# onThyristor.net
KiCad netlist of a schematic drawn in Altium Designer
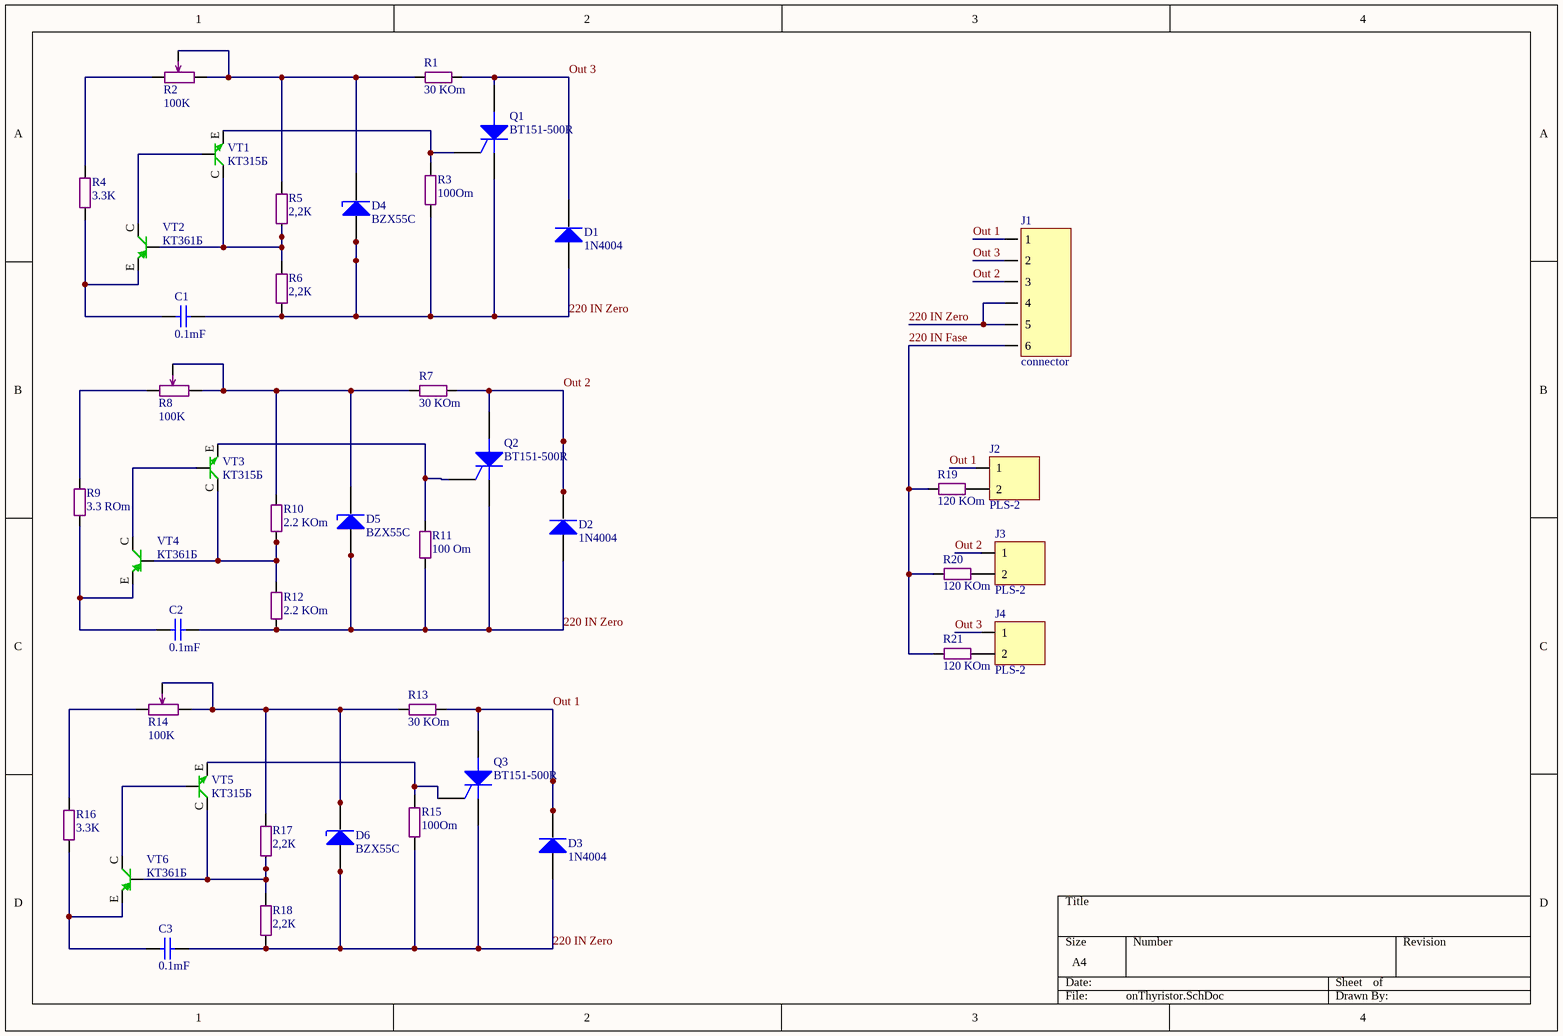
[diagram p0: onThyristor.SchDoc]

(export (version "E")
  (design (tool "Eeschema 10.0.6"))
  (components
    (comp (ref "C1")
      (value "0.1mF")
      (footprint "Capacitor:Cap P5.08MM (3p) disk2")
      (description "Capacitor")
      (libsource (lib "Capacitor") (part "Cap Ceramic"))
    )
    (comp (ref "C2")
      (value "0.1mF")
      (footprint "Capacitor:Cap P5.08MM (3p) disk2")
      (description "Capacitor")
      (libsource (lib "Capacitor") (part "Cap Ceramic"))
    )
    (comp (ref "C3")
      (value "0.1mF")
      (footprint "Capacitor:Cap P5.08MM (3p) disk2")
      (description "Capacitor")
      (libsource (lib "Capacitor") (part "Cap Ceramic"))
    )
    (comp (ref "D1")
      (value "1N4004")
      (footprint "Diodes:Diode DO-35")
      (description "1 Amp General Purpose Rectifier")
      (libsource (lib "Diodes") (part "Diode 1N4004"))
    )
    (comp (ref "D2")
      (value "1N4004")
      (footprint "Diodes:Diode DO-35")
      (description "1 Amp General Purpose Rectifier")
      (libsource (lib "Diodes") (part "Diode 1N4004"))
    )
    (comp (ref "D3")
      (value "1N4004")
      (footprint "Diodes:Diode DO-35")
      (description "1 Amp General Purpose Rectifier")
      (libsource (lib "Diodes") (part "Diode 1N4004"))
    )
    (comp (ref "D4")
      (value "BZX55C")
      (footprint "Diodes:Diode DO-35")
      (description "1 Amp General Purpose Rectifier")
      (libsource (lib "Diodes") (part "Stabistor BZX55C"))
    )
    (comp (ref "D5")
      (value "BZX55C")
      (footprint "Diodes:Diode DO-35")
      (description "1 Amp General Purpose Rectifier")
      (libsource (lib "Diodes") (part "Stabistor BZX55C"))
    )
    (comp (ref "D6")
      (value "BZX55C")
      (footprint "Diodes:Diode DO-35")
      (description "1 Amp General Purpose Rectifier")
      (libsource (lib "Diodes") (part "Stabistor BZX55C"))
    )
    (comp (ref "J1")
      (value "connector")
      (footprint "Connector:Molex Mini-Fit Jr - 6Pin R")
      (description "Right, Dbl line, Female")
      (libsource (lib "Connector") (part "Molex Mini-Fit Jr - 6 pin - R"))
    )
    (comp (ref "J2")
      (value "PLS-2")
      (footprint "Connector:Line 2.54 x 2")
      (description "Vert, Sgl line, Male")
      (libsource (lib "Connector") (part "PLS-2"))
    )
    (comp (ref "J3")
      (value "PLS-2")
      (footprint "Connector:Line 2.54 x 2")
      (description "Vert, Sgl line, Male")
      (libsource (lib "Connector") (part "PLS-2"))
    )
    (comp (ref "J4")
      (value "PLS-2")
      (footprint "Connector:Line 2.54 x 2")
      (description "Vert, Sgl line, Male")
      (libsource (lib "Connector") (part "PLS-2"))
    )
    (comp (ref "Q1")
      (value "BT151-500R")
      (footprint "GeneralCases:TO220-2")
      (description "Thyristor")
      (libsource (lib "Diodes") (part "Th BT151-500R"))
    )
    (comp (ref "Q2")
      (value "BT151-500R")
      (footprint "GeneralCases:TO220-2")
      (description "Thyristor")
      (libsource (lib "Diodes") (part "Th BT151-500R"))
    )
    (comp (ref "Q3")
      (value "BT151-500R")
      (footprint "GeneralCases:TO220-2")
      (description "Thyristor")
      (libsource (lib "Diodes") (part "Th BT151-500R"))
    )
    (comp (ref "R1")
      (value "30 KOm")
      (footprint "PassiveComponents:Res 5W L22mm, p30mm")
      (description "5W Cement")
      (libsource (lib "PassiveComponents") (part "Res 5W"))
    )
    (comp (ref "R2")
      (value "100K")
      (footprint "bj Lib:PinLine 3x")
      (libsource (lib "bj Lib") (part "Resistor Adj"))
    )
    (comp (ref "R3")
      (value "100Om")
      (footprint "PassiveComponents:Res p7.62 (4p) 0.25w")
      (libsource (lib "bj Lib") (part "Resistor"))
    )
    (comp (ref "R4")
      (value "3.3K")
      (footprint "PassiveComponents:Res p7.62 (4p) 0.25w")
      (libsource (lib "bj Lib") (part "Resistor"))
    )
    (comp (ref "R5")
      (value "2,2К")
      (footprint "PassiveComponents:Res p7.62 (4p) 0.25w")
      (libsource (lib "bj Lib") (part "Resistor"))
    )
    (comp (ref "R6")
      (value "2,2К")
      (footprint "PassiveComponents:Res p7.62 (4p) 0.25w")
      (libsource (lib "bj Lib") (part "Resistor"))
    )
    (comp (ref "R7")
      (value "30 KOm")
      (footprint "PassiveComponents:Res 5W L22mm, p30mm")
      (description "5W Cement")
      (libsource (lib "PassiveComponents") (part "Res 5W"))
    )
    (comp (ref "R8")
      (value "100K")
      (footprint "bj Lib:PinLine 3x")
      (libsource (lib "bj Lib") (part "Resistor Adj"))
    )
    (comp (ref "R9")
      (value "3.3 ROm")
      (footprint "PassiveComponents:Res p7.62 (4p) 0.25w")
      (libsource (lib "PassiveComponents") (part "Res SMD 0603"))
    )
    (comp (ref "R10")
      (value "2.2 KOm")
      (footprint "PassiveComponents:Res p7.62 (4p) 0.25w")
      (libsource (lib "PassiveComponents") (part "Res SMD 0603"))
    )
    (comp (ref "R11")
      (value "100 Om")
      (footprint "PassiveComponents:Res p7.62 (4p) 0.25w")
      (libsource (lib "PassiveComponents") (part "Res SMD 0603"))
    )
    (comp (ref "R12")
      (value "2.2 KOm")
      (footprint "PassiveComponents:Res p7.62 (4p) 0.25w")
      (libsource (lib "PassiveComponents") (part "Res SMD 0603"))
    )
    (comp (ref "R13")
      (value "30 KOm")
      (footprint "PassiveComponents:Res 5W L22mm, p30mm")
      (description "5W Cement")
      (libsource (lib "PassiveComponents") (part "Res 5W"))
    )
    (comp (ref "R14")
      (value "100K")
      (footprint "bj Lib:PinLine 3x")
      (libsource (lib "bj Lib") (part "Resistor Adj"))
    )
    (comp (ref "R15")
      (value "100Om")
      (footprint "PassiveComponents:SMD 0805 (2012)")
      (libsource (lib "bj Lib") (part "Resistor"))
    )
    (comp (ref "R16")
      (value "3.3K")
      (footprint "PassiveComponents:Res p7.62 (4p) 0.25w")
      (libsource (lib "bj Lib") (part "Resistor"))
    )
    (comp (ref "R17")
      (value "2,2К")
      (footprint "PassiveComponents:Res p7.62 (4p) 0.25w")
      (libsource (lib "bj Lib") (part "Resistor"))
    )
    (comp (ref "R18")
      (value "2,2К")
      (footprint "bj Lib:Res p7.62 (4p)")
      (libsource (lib "bj Lib") (part "Resistor"))
    )
    (comp (ref "R19")
      (value "120 KOm")
      (footprint "PassiveComponents:SMD 1206 (3216)")
      (libsource (lib "PassiveComponents") (part "Res Carbon"))
    )
    (comp (ref "R20")
      (value "120 KOm")
      (footprint "PassiveComponents:SMD 1206 (3216)")
      (libsource (lib "PassiveComponents") (part "Res Carbon"))
    )
    (comp (ref "R21")
      (value "120 KOm")
      (footprint "PassiveComponents:SMD 1206 (3216)")
      (libsource (lib "PassiveComponents") (part "Res Carbon"))
    )
    (comp (ref "VT1") (value "КТ315Б") (footprint "Trnstr (3p) ECB") (libsource (lib "bj Lib") (part "NPN")))
    (comp (ref "VT2")
      (value "КТ361Б")
      (footprint "bj Lib:Trnstr (3p) ECB")
      (libsource (lib "bj Lib") (part "PNP"))
    )
    (comp (ref "VT3") (value "КТ315Б") (footprint "Trnstr (3p) ECB") (libsource (lib "bj Lib") (part "NPN")))
    (comp (ref "VT4")
      (value "КТ361Б")
      (footprint "bj Lib:Trnstr (3p) ECB")
      (libsource (lib "bj Lib") (part "PNP"))
    )
    (comp (ref "VT5") (value "КТ315Б") (footprint "Trnstr (3p) ECB") (libsource (lib "bj Lib") (part "NPN")))
    (comp (ref "VT6")
      (value "КТ361Б")
      (footprint "bj Lib:Trnstr (3p) ECB")
      (libsource (lib "bj Lib") (part "PNP"))
    )
  )
  (nets
    (net (code "1") (name "/220 IN Fase") (class "Default")
      (node (ref "J1") (pin "6") (pinfunction "6_6") (pintype "passive"))
      (node (ref "R19") (pin "1") (pinfunction "1_1") (pintype "passive"))
      (node (ref "R20") (pin "1") (pinfunction "1_1") (pintype "passive"))
      (node (ref "R21") (pin "1") (pinfunction "1_1") (pintype "passive"))
    )
    (net (code "2") (name "/220 IN Zero") (class "Default")
      (node (ref "C1") (pin "2") (pinfunction "2_2") (pintype "passive"))
      (node (ref "C2") (pin "2") (pinfunction "2_2") (pintype "passive"))
      (node (ref "C3") (pin "2") (pinfunction "2_2") (pintype "passive"))
      (node (ref "D1") (pin "A") (pinfunction "A_A") (pintype "passive"))
      (node (ref "D2") (pin "A") (pinfunction "A_A") (pintype "passive"))
      (node (ref "D3") (pin "A") (pinfunction "A_A") (pintype "passive"))
      (node (ref "D4") (pin "A") (pinfunction "A_A") (pintype "passive"))
      (node (ref "D5") (pin "A") (pinfunction "A_A") (pintype "passive"))
      (node (ref "D6") (pin "A") (pinfunction "A_A") (pintype "passive"))
      (node (ref "J1") (pin "4") (pinfunction "4_4") (pintype "passive"))
      (node (ref "J1") (pin "5") (pinfunction "5_5") (pintype "passive"))
      (node (ref "Q1") (pin "1") (pinfunction "K_1") (pintype "passive"))
      (node (ref "Q2") (pin "1") (pinfunction "K_1") (pintype "passive"))
      (node (ref "Q3") (pin "1") (pinfunction "K_1") (pintype "passive"))
      (node (ref "R11") (pin "1") (pinfunction "1_1") (pintype "passive"))
      (node (ref "R12") (pin "1") (pinfunction "1_1") (pintype "passive"))
      (node (ref "R15") (pin "1") (pinfunction "1_1") (pintype "passive"))
      (node (ref "R18") (pin "1") (pinfunction "1_1") (pintype "passive"))
      (node (ref "R3") (pin "1") (pinfunction "1_1") (pintype "passive"))
      (node (ref "R6") (pin "1") (pinfunction "1_1") (pintype "passive"))
    )
    (net (code "3") (name "/Out 1") (class "Default")
      (node (ref "D3") (pin "K") (pinfunction "K_K") (pintype "passive"))
      (node (ref "J1") (pin "1") (pinfunction "1_1") (pintype "passive"))
      (node (ref "J2") (pin "1") (pinfunction "1_1") (pintype "passive"))
      (node (ref "Q3") (pin "2") (pinfunction "A_2") (pintype "passive"))
      (node (ref "R13") (pin "2") (pinfunction "2_2") (pintype "passive"))
    )
    (net (code "4") (name "/Out 2") (class "Default")
      (node (ref "D2") (pin "K") (pinfunction "K_K") (pintype "passive"))
      (node (ref "J1") (pin "3") (pinfunction "3_3") (pintype "passive"))
      (node (ref "J3") (pin "1") (pinfunction "1_1") (pintype "passive"))
      (node (ref "Q2") (pin "2") (pinfunction "A_2") (pintype "passive"))
      (node (ref "R7") (pin "2") (pinfunction "2_2") (pintype "passive"))
    )
    (net (code "5") (name "/Out 3") (class "Default")
      (node (ref "D1") (pin "K") (pinfunction "K_K") (pintype "passive"))
      (node (ref "J1") (pin "2") (pinfunction "2_2") (pintype "passive"))
      (node (ref "J4") (pin "1") (pinfunction "1_1") (pintype "passive"))
      (node (ref "Q1") (pin "2") (pinfunction "A_2") (pintype "passive"))
      (node (ref "R1") (pin "2") (pinfunction "2_2") (pintype "passive"))
    )
    (net (code "6") (name "Net-(C1-Pad1)") (class "Default")
      (node (ref "C1") (pin "1") (pinfunction "1_1") (pintype "passive"))
      (node (ref "R4") (pin "1") (pinfunction "1_1") (pintype "passive"))
      (node (ref "VT2") (pin "E") (pinfunction "E_E") (pintype "passive"))
    )
    (net (code "7") (name "Net-(C2-Pad1)") (class "Default")
      (node (ref "C2") (pin "1") (pinfunction "1_1") (pintype "passive"))
      (node (ref "R9") (pin "1") (pinfunction "1_1") (pintype "passive"))
      (node (ref "VT4") (pin "E") (pinfunction "E_E") (pintype "passive"))
    )
    (net (code "8") (name "Net-(C3-Pad1)") (class "Default")
      (node (ref "C3") (pin "1") (pinfunction "1_1") (pintype "passive"))
      (node (ref "R16") (pin "1") (pinfunction "1_1") (pintype "passive"))
      (node (ref "VT6") (pin "E") (pinfunction "E_E") (pintype "passive"))
    )
    (net (code "9") (name "Net-(D4-PadK)") (class "Default")
      (node (ref "D4") (pin "K") (pinfunction "K_K") (pintype "passive"))
      (node (ref "R1") (pin "1") (pinfunction "1_1") (pintype "passive"))
      (node (ref "R2") (pin "2") (pinfunction "2_2") (pintype "passive"))
      (node (ref "R2") (pin "3") (pinfunction "3_3") (pintype "passive"))
      (node (ref "R5") (pin "2") (pinfunction "2_2") (pintype "passive"))
    )
    (net (code "10") (name "Net-(D5-PadK)") (class "Default")
      (node (ref "D5") (pin "K") (pinfunction "K_K") (pintype "passive"))
      (node (ref "R10") (pin "2") (pinfunction "2_2") (pintype "passive"))
      (node (ref "R7") (pin "1") (pinfunction "1_1") (pintype "passive"))
      (node (ref "R8") (pin "2") (pinfunction "2_2") (pintype "passive"))
      (node (ref "R8") (pin "3") (pinfunction "3_3") (pintype "passive"))
    )
    (net (code "11") (name "Net-(D6-PadK)") (class "Default")
      (node (ref "D6") (pin "K") (pinfunction "K_K") (pintype "passive"))
      (node (ref "R13") (pin "1") (pinfunction "1_1") (pintype "passive"))
      (node (ref "R14") (pin "2") (pinfunction "2_2") (pintype "passive"))
      (node (ref "R14") (pin "3") (pinfunction "3_3") (pintype "passive"))
      (node (ref "R17") (pin "2") (pinfunction "2_2") (pintype "passive"))
    )
    (net (code "12") (name "Net-(J2-Pad2)") (class "Default")
      (node (ref "J2") (pin "2") (pinfunction "2_2") (pintype "passive"))
      (node (ref "R19") (pin "2") (pinfunction "2_2") (pintype "passive"))
    )
    (net (code "13") (name "Net-(J3-Pad2)") (class "Default")
      (node (ref "J3") (pin "2") (pinfunction "2_2") (pintype "passive"))
      (node (ref "R20") (pin "2") (pinfunction "2_2") (pintype "passive"))
    )
    (net (code "14") (name "Net-(J4-Pad2)") (class "Default")
      (node (ref "J4") (pin "2") (pinfunction "2_2") (pintype "passive"))
      (node (ref "R21") (pin "2") (pinfunction "2_2") (pintype "passive"))
    )
    (net (code "15") (name "Net-(Q1-G)") (class "Default")
      (node (ref "Q1") (pin "3") (pinfunction "G_3") (pintype "passive"))
      (node (ref "R3") (pin "2") (pinfunction "2_2") (pintype "passive"))
      (node (ref "VT1") (pin "E") (pinfunction "E_E") (pintype "passive"))
    )
    (net (code "16") (name "Net-(Q2-G)") (class "Default")
      (node (ref "Q2") (pin "3") (pinfunction "G_3") (pintype "passive"))
      (node (ref "R11") (pin "2") (pinfunction "2_2") (pintype "passive"))
      (node (ref "VT3") (pin "E") (pinfunction "E_E") (pintype "passive"))
    )
    (net (code "17") (name "Net-(Q3-G)") (class "Default")
      (node (ref "Q3") (pin "3") (pinfunction "G_3") (pintype "passive"))
      (node (ref "R15") (pin "2") (pinfunction "2_2") (pintype "passive"))
      (node (ref "VT5") (pin "E") (pinfunction "E_E") (pintype "passive"))
    )
    (net (code "18") (name "Net-(R2-Pad1)") (class "Default")
      (node (ref "R2") (pin "1") (pinfunction "1_1") (pintype "passive"))
      (node (ref "R4") (pin "2") (pinfunction "2_2") (pintype "passive"))
    )
    (net (code "19") (name "Net-(R5-Pad1)") (class "Default")
      (node (ref "R5") (pin "1") (pinfunction "1_1") (pintype "passive"))
      (node (ref "R6") (pin "2") (pinfunction "2_2") (pintype "passive"))
      (node (ref "VT1") (pin "C") (pinfunction "C_C") (pintype "passive"))
      (node (ref "VT2") (pin "B") (pinfunction "B_B") (pintype "passive"))
    )
    (net (code "20") (name "Net-(R8-Pad1)") (class "Default")
      (node (ref "R8") (pin "1") (pinfunction "1_1") (pintype "passive"))
      (node (ref "R9") (pin "2") (pinfunction "2_2") (pintype "passive"))
    )
    (net (code "21") (name "Net-(R10-Pad1)") (class "Default")
      (node (ref "R10") (pin "1") (pinfunction "1_1") (pintype "passive"))
      (node (ref "R12") (pin "2") (pinfunction "2_2") (pintype "passive"))
      (node (ref "VT3") (pin "C") (pinfunction "C_C") (pintype "passive"))
      (node (ref "VT4") (pin "B") (pinfunction "B_B") (pintype "passive"))
    )
    (net (code "22") (name "Net-(R14-Pad1)") (class "Default")
      (node (ref "R14") (pin "1") (pinfunction "1_1") (pintype "passive"))
      (node (ref "R16") (pin "2") (pinfunction "2_2") (pintype "passive"))
    )
    (net (code "23") (name "Net-(R17-Pad1)") (class "Default")
      (node (ref "R17") (pin "1") (pinfunction "1_1") (pintype "passive"))
      (node (ref "R18") (pin "2") (pinfunction "2_2") (pintype "passive"))
      (node (ref "VT5") (pin "C") (pinfunction "C_C") (pintype "passive"))
      (node (ref "VT6") (pin "B") (pinfunction "B_B") (pintype "passive"))
    )
    (net (code "24") (name "Net-(VT1-PadB)") (class "Default")
      (node (ref "VT1") (pin "B") (pinfunction "B_B") (pintype "passive"))
      (node (ref "VT2") (pin "C") (pinfunction "C_C") (pintype "passive"))
    )
    (net (code "25") (name "Net-(VT3-PadB)") (class "Default")
      (node (ref "VT3") (pin "B") (pinfunction "B_B") (pintype "passive"))
      (node (ref "VT4") (pin "C") (pinfunction "C_C") (pintype "passive"))
    )
    (net (code "26") (name "Net-(VT5-PadB)") (class "Default")
      (node (ref "VT5") (pin "B") (pinfunction "B_B") (pintype "passive"))
      (node (ref "VT6") (pin "C") (pinfunction "C_C") (pintype "passive"))
    )
  )
)
